# keyboard_trans_flipped.net
KiCad netlist of a schematic drawn in EAGLE
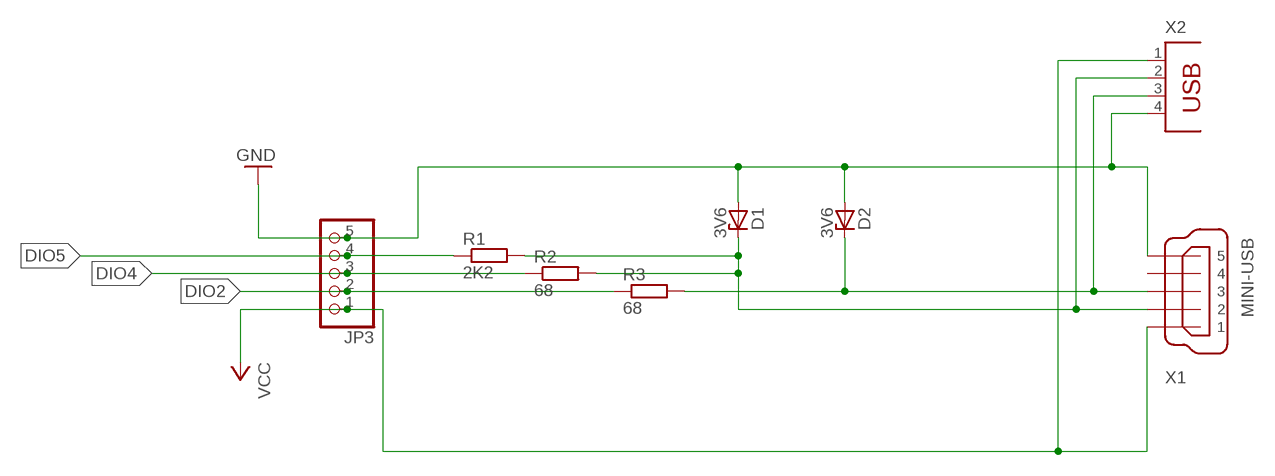
[diagram p0: schematic, sheet 1]

(export (version "E")
  (design (tool "Eeschema 10.0.6"))
  (components
    (comp (ref "D1")
      (value "3V6")
      (footprint "eagle-import:DO35Z10")
      (libsource (lib "eagle-import") (part "ZPD"))
    )
    (comp (ref "D2")
      (value "3V6")
      (footprint "eagle-import:DO35Z10")
      (libsource (lib "eagle-import") (part "ZPD"))
    )
    (comp (ref "JP3")
      (value "PINHD-1X5")
      (footprint "eagle-import:1X05")
      (libsource (lib "eagle-import") (part "PINHD-1X5"))
    )
    (comp (ref "R1")
      (value "2K2")
      (footprint "eagle-import:0204_5")
      (libsource (lib "eagle-import") (part "R-EU_0204/5"))
    )
    (comp (ref "R2")
      (value "68")
      (footprint "eagle-import:0204_5")
      (libsource (lib "eagle-import") (part "R-EU_0204/5"))
    )
    (comp (ref "R3")
      (value "68")
      (footprint "eagle-import:0204_5")
      (libsource (lib "eagle-import") (part "R-EU_0204/5"))
    )
    (comp (ref "X1")
      (value "MINI-USB")
      (footprint "eagle-import:UX60-MB-5S8")
      (libsource (lib "eagle-import") (part "MINI-USB-UX60-MB-5S8"))
    )
    (comp (ref "X2")
      (value "PN61729")
      (footprint "eagle-import:PN61729")
      (libsource (lib "eagle-import") (part "PN61729"))
    )
  )
  (nets
    (net (code "1") (name "DIO2") (class "Default")
      (node (ref "JP3") (pin "2") (pinfunction "2_2") (pintype "passive"))
      (node (ref "R3") (pin "1") (pinfunction "1_1") (pintype "passive"))
    )
    (net (code "2") (name "DIO4") (class "Default")
      (node (ref "JP3") (pin "3") (pinfunction "3_3") (pintype "passive"))
      (node (ref "R2") (pin "1") (pinfunction "1_1") (pintype "passive"))
    )
    (net (code "3") (name "DIO5") (class "Default")
      (node (ref "JP3") (pin "4") (pinfunction "4_4") (pintype "passive"))
      (node (ref "R1") (pin "1") (pinfunction "1_1") (pintype "passive"))
    )
    (net (code "4") (name "GND") (class "Default")
      (node (ref "D1") (pin "A") (pinfunction "A_A") (pintype "passive"))
      (node (ref "D2") (pin "A") (pinfunction "A_A") (pintype "passive"))
      (node (ref "JP3") (pin "5") (pinfunction "5_5") (pintype "passive"))
      (node (ref "X1") (pin "5") (pinfunction "5_5") (pintype "input"))
      (node (ref "X2") (pin "4") (pinfunction "4_4") (pintype "passive"))
    )
    (net (code "5") (name "Net-(D1-PadC)") (class "Default")
      (node (ref "D1") (pin "C") (pinfunction "C_C") (pintype "passive"))
      (node (ref "R1") (pin "2") (pinfunction "2_2") (pintype "passive"))
      (node (ref "R2") (pin "2") (pinfunction "2_2") (pintype "passive"))
      (node (ref "X1") (pin "2") (pinfunction "2_2") (pintype "input"))
      (node (ref "X2") (pin "2") (pinfunction "2_2") (pintype "passive"))
    )
    (net (code "6") (name "Net-(D2-PadC)") (class "Default")
      (node (ref "D2") (pin "C") (pinfunction "C_C") (pintype "passive"))
      (node (ref "R3") (pin "2") (pinfunction "2_2") (pintype "passive"))
      (node (ref "X1") (pin "3") (pinfunction "3_3") (pintype "input"))
      (node (ref "X2") (pin "3") (pinfunction "3_3") (pintype "passive"))
    )
    (net (code "7") (name "VCC") (class "Default")
      (node (ref "JP3") (pin "1") (pinfunction "1_1") (pintype "passive"))
      (node (ref "X1") (pin "1") (pinfunction "1_1") (pintype "input"))
      (node (ref "X2") (pin "1") (pinfunction "1_1") (pintype "passive"))
    )
    (net (code "8") (name "unconnected-(X1-Pad4)") (class "Default")
      (node (ref "X1") (pin "4") (pinfunction "4_4") (pintype "input"))
    )
  )
)
